# Esquema.net
KiCad netlist of a schematic drawn in EAGLE
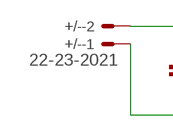
[diagram p0: schematic, sheet 1, part 1 of 2]
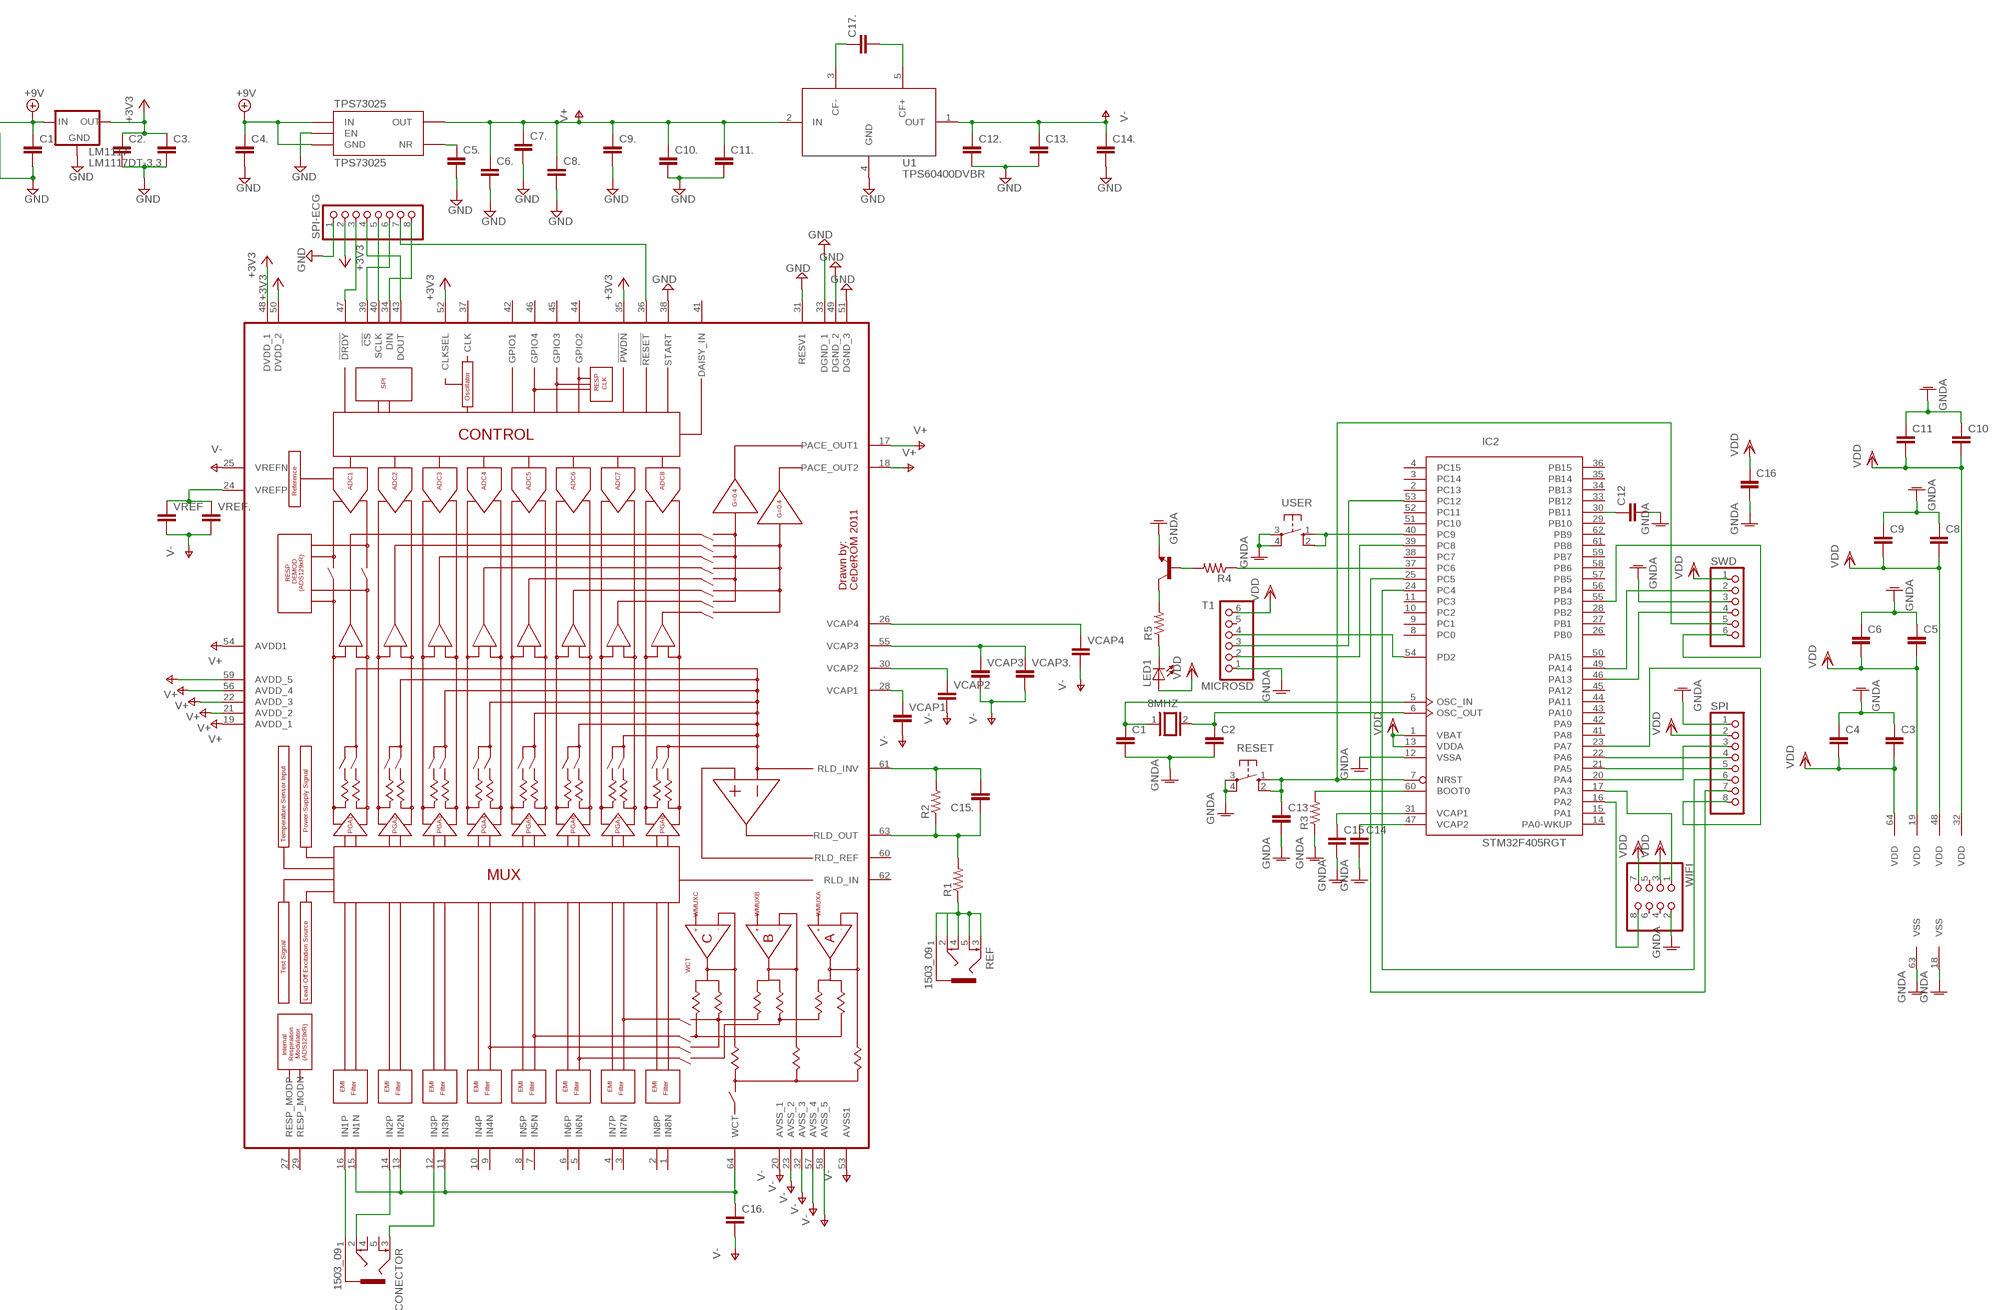
[diagram p1: schematic, sheet 1, part 2 of 2]

(export (version "E")
  (design (tool "Eeschema 10.0.6"))
  (components
    (comp (ref "+/-")
      (value "22-23-2021")
      (footprint "eagle-import:22-23-2021")
      (fields (field (name "MF") "MOLEX"))
      (libsource (lib "eagle-import") (part "22-23-2021"))
    )
    (comp (ref "8MHZ")
      (value "XTAL/S")
      (footprint "eagle-import:QS")
      (libsource (lib "eagle-import") (part "XTAL/S"))
    )
    (comp (ref "C1")
      (value "C-EUC0805K")
      (footprint "eagle-import:C0805K")
      (libsource (lib "eagle-import") (part "resistor_348_C-EUC0805K"))
    )
    (comp (ref "C1.")
      (value "C-EUC1206K")
      (footprint "eagle-import:C1206K")
      (libsource (lib "eagle-import") (part "C-EUC1206K"))
    )
    (comp (ref "C2")
      (value "C-EUC0805K")
      (footprint "eagle-import:C0805K")
      (libsource (lib "eagle-import") (part "resistor_348_C-EUC0805K"))
    )
    (comp (ref "C2.")
      (value "C-EUC1206K")
      (footprint "eagle-import:C1206K")
      (libsource (lib "eagle-import") (part "C-EUC1206K"))
    )
    (comp (ref "C3")
      (value "C-EUC1206K")
      (footprint "eagle-import:C1206K")
      (libsource (lib "eagle-import") (part "resistor_348_C-EUC1206K"))
    )
    (comp (ref "C3.")
      (value "C-EUC1206K")
      (footprint "eagle-import:C1206K")
      (libsource (lib "eagle-import") (part "C-EUC1206K"))
    )
    (comp (ref "C4")
      (value "C-EUC1206K")
      (footprint "eagle-import:C1206K")
      (libsource (lib "eagle-import") (part "resistor_348_C-EUC1206K"))
    )
    (comp (ref "C4.")
      (value "C-EUC1206K")
      (footprint "eagle-import:C1206K")
      (libsource (lib "eagle-import") (part "C-EUC1206K"))
    )
    (comp (ref "C5")
      (value "C-EUC1206K")
      (footprint "eagle-import:C1206K")
      (libsource (lib "eagle-import") (part "resistor_348_C-EUC1206K"))
    )
    (comp (ref "C5.")
      (value "C-EUC0805K")
      (footprint "eagle-import:C0805K")
      (libsource (lib "eagle-import") (part "C-EUC0805K"))
    )
    (comp (ref "C6")
      (value "C-EUC1206K")
      (footprint "eagle-import:C1206K")
      (libsource (lib "eagle-import") (part "resistor_348_C-EUC1206K"))
    )
    (comp (ref "C6.")
      (value "C-EUC1206K")
      (footprint "eagle-import:C1206K")
      (libsource (lib "eagle-import") (part "C-EUC1206K"))
    )
    (comp (ref "C7.")
      (value "C-EUC1206K")
      (footprint "eagle-import:C1206K")
      (libsource (lib "eagle-import") (part "C-EUC1206K"))
    )
    (comp (ref "C8")
      (value "C-EUC1206K")
      (footprint "eagle-import:C1206K")
      (libsource (lib "eagle-import") (part "resistor_348_C-EUC1206K"))
    )
    (comp (ref "C8.")
      (value "C-EUC1206K")
      (footprint "eagle-import:C1206K")
      (libsource (lib "eagle-import") (part "C-EUC1206K"))
    )
    (comp (ref "C9")
      (value "C-EUC1206K")
      (footprint "eagle-import:C1206K")
      (libsource (lib "eagle-import") (part "resistor_348_C-EUC1206K"))
    )
    (comp (ref "C9.")
      (value "C-EUC1206K")
      (footprint "eagle-import:C1206K")
      (libsource (lib "eagle-import") (part "C-EUC1206K"))
    )
    (comp (ref "C10")
      (value "C-EUC1206K")
      (footprint "eagle-import:C1206K")
      (libsource (lib "eagle-import") (part "resistor_348_C-EUC1206K"))
    )
    (comp (ref "C10.")
      (value "C-EUC1206K")
      (footprint "eagle-import:C1206K")
      (libsource (lib "eagle-import") (part "C-EUC1206K"))
    )
    (comp (ref "C11")
      (value "C-EUC1206K")
      (footprint "eagle-import:C1206K")
      (libsource (lib "eagle-import") (part "resistor_348_C-EUC1206K"))
    )
    (comp (ref "C11.")
      (value "C-EUC1206K")
      (footprint "eagle-import:C1206K")
      (libsource (lib "eagle-import") (part "C-EUC1206K"))
    )
    (comp (ref "C12")
      (value "C-EUC1206K")
      (footprint "eagle-import:C1206K")
      (libsource (lib "eagle-import") (part "resistor_348_C-EUC1206K"))
    )
    (comp (ref "C12.")
      (value "C-EUC1206K")
      (footprint "eagle-import:C1206K")
      (libsource (lib "eagle-import") (part "C-EUC1206K"))
    )
    (comp (ref "C13")
      (value "C-EUC1206K")
      (footprint "eagle-import:C1206K")
      (libsource (lib "eagle-import") (part "resistor_348_C-EUC1206K"))
    )
    (comp (ref "C13.")
      (value "C-EUC1206K")
      (footprint "eagle-import:C1206K")
      (libsource (lib "eagle-import") (part "C-EUC1206K"))
    )
    (comp (ref "C14")
      (value "C-EUC1206K")
      (footprint "eagle-import:C1206K")
      (libsource (lib "eagle-import") (part "resistor_348_C-EUC1206K"))
    )
    (comp (ref "C14.")
      (value "C-EUC1206K")
      (footprint "eagle-import:C1206K")
      (libsource (lib "eagle-import") (part "C-EUC1206K"))
    )
    (comp (ref "C15")
      (value "C-EUC1206K")
      (footprint "eagle-import:C1206K")
      (libsource (lib "eagle-import") (part "resistor_348_C-EUC1206K"))
    )
    (comp (ref "C15.")
      (value "C-EUC1206K")
      (footprint "eagle-import:C1206K")
      (libsource (lib "eagle-import") (part "resistor_348_C-EUC1206K"))
    )
    (comp (ref "C16")
      (value "C-EUC1206K")
      (footprint "eagle-import:C1206K")
      (libsource (lib "eagle-import") (part "resistor_348_C-EUC1206K"))
    )
    (comp (ref "C16.")
      (value "C-EUC0805K")
      (footprint "eagle-import:C0805K")
      (libsource (lib "eagle-import") (part "resistor_348_C-EUC0805K"))
    )
    (comp (ref "C17.")
      (value "C-EUC1206K")
      (footprint "eagle-import:C1206K")
      (libsource (lib "eagle-import") (part "C-EUC1206K"))
    )
    (comp (ref "CONECTOR")
      (value "1503_09")
      (footprint "eagle-import:1503_09")
      (libsource (lib "eagle-import") (part "1503_09"))
    )
    (comp (ref "IC2")
      (value "STM32F405RGT")
      (footprint "eagle-import:LQFP64")
      (libsource (lib "eagle-import") (part "STM32F405RTG"))
    )
    (comp (ref "LED1")
      (value "LEDCHIP-LED0805")
      (footprint "eagle-import:CHIP-LED0805")
      (libsource (lib "eagle-import") (part "LEDCHIP-LED0805"))
    )
    (comp (ref "LM1117")
      (value "LM1117DT-3.3")
      (footprint "eagle-import:TO252")
      (fields (field (name "MF") "Texas Instruments"))
      (libsource (lib "eagle-import") (part "LM1117?-DT3.3"))
    )
    (comp (ref "MICROSD")
      (value "PINHD-1X6")
      (footprint "eagle-import:1X06")
      (libsource (lib "eagle-import") (part "PINHD-1X6"))
    )
    (comp (ref "R1")
      (value "R-US_R1206")
      (footprint "eagle-import:R1206")
      (libsource (lib "eagle-import") (part "R-US_R1206"))
    )
    (comp (ref "R2")
      (value "R-US_R1206")
      (footprint "eagle-import:R1206")
      (libsource (lib "eagle-import") (part "R-US_R1206"))
    )
    (comp (ref "R3")
      (value "R-US_R1206")
      (footprint "eagle-import:R1206")
      (libsource (lib "eagle-import") (part "R-US_R1206"))
    )
    (comp (ref "R4")
      (value "R-US_R1206")
      (footprint "eagle-import:R1206")
      (libsource (lib "eagle-import") (part "R-US_R1206"))
    )
    (comp (ref "R5")
      (value "R-US_R1206")
      (footprint "eagle-import:R1206")
      (libsource (lib "eagle-import") (part "R-US_R1206"))
    )
    (comp (ref "REF")
      (value "1503_09")
      (footprint "eagle-import:1503_09")
      (libsource (lib "eagle-import") (part "1503_09"))
    )
    (comp (ref "RESET")
      (value "10-XX")
      (footprint "eagle-import:B3F-10XX")
      (fields (field (name "MPN") "B3F-1000"))
      (libsource (lib "eagle-import") (part "10-XX"))
    )
    (comp (ref "SPI")
      (value "PINHD-1X8")
      (footprint "eagle-import:1X08")
      (libsource (lib "eagle-import") (part "PINHD-1X8"))
    )
    (comp (ref "SPI-ECG")
      (value "PINHD-1X8")
      (footprint "eagle-import:1X08")
      (libsource (lib "eagle-import") (part "PINHD-1X8"))
    )
    (comp (ref "SWD")
      (value "PINHD-1X6")
      (footprint "eagle-import:1X06")
      (libsource (lib "eagle-import") (part "PINHD-1X6"))
    )
    (comp (ref "T1")
      (value "MMBT2222ALT1-NPN-SOT23-BEC")
      (footprint "eagle-import:SOT23-BEC")
      (libsource (lib "eagle-import") (part "-NPN-SOT23-BECMMBT2222ALT1"))
    )
    (comp (ref "TPS73025")
      (value "TPS73025")
      (footprint "eagle-import:SOT23-5L")
      (libsource (lib "eagle-import") (part "TPS73025"))
    )
    (comp (ref "U$1")
      (value "ADS1298*PAG*")
      (footprint "eagle-import:TQFP64")
      (libsource (lib "eagle-import") (part "ADS1298PAG"))
    )
    (comp (ref "U1")
      (value "TPS60400DVBR")
      (footprint "eagle-import:SOT23-5")
      (libsource (lib "eagle-import") (part "TPS60400DVBR"))
    )
    (comp (ref "USER")
      (value "10-XX")
      (footprint "eagle-import:B3F-10XX")
      (fields (field (name "MPN") "B3F-1000"))
      (libsource (lib "eagle-import") (part "10-XX"))
    )
    (comp (ref "VCAP1")
      (value "C-EUC0805K")
      (footprint "eagle-import:C0805K")
      (libsource (lib "eagle-import") (part "C-EUC0805K"))
    )
    (comp (ref "VCAP2")
      (value "C-EUC1206K")
      (footprint "eagle-import:C1206K")
      (libsource (lib "eagle-import") (part "C-EUC1206K"))
    )
    (comp (ref "VCAP3")
      (value "C-EUC1206K")
      (footprint "eagle-import:C1206K")
      (libsource (lib "eagle-import") (part "C-EUC1206K"))
    )
    (comp (ref "VCAP3.")
      (value "C-EUC1206K")
      (footprint "eagle-import:C1206K")
      (libsource (lib "eagle-import") (part "C-EUC1206K"))
    )
    (comp (ref "VCAP4")
      (value "C-EUC1206K")
      (footprint "eagle-import:C1206K")
      (libsource (lib "eagle-import") (part "C-EUC1206K"))
    )
    (comp (ref "VREF")
      (value "C-EUC1206K")
      (footprint "eagle-import:C1206K")
      (libsource (lib "eagle-import") (part "C-EUC1206K"))
    )
    (comp (ref "VREF.")
      (value "C-EUC1206K")
      (footprint "eagle-import:C1206K")
      (libsource (lib "eagle-import") (part "C-EUC1206K"))
    )
    (comp (ref "WIFI")
      (value "PINHD-2X4")
      (footprint "eagle-import:2X04")
      (libsource (lib "eagle-import") (part "PINHD-2X4"))
    )
  )
  (nets
    (net (code "1") (name "+3V3") (class "Default")
      (node (ref "C2.") (pin "1") (pinfunction "1_1") (pintype "passive"))
      (node (ref "C3.") (pin "1") (pinfunction "1_1") (pintype "passive"))
      (node (ref "LM1117") (pin "3") (pinfunction "OUT_3") (pintype "passive"))
      (node (ref "SPI-ECG") (pin "2") (pinfunction "2_2") (pintype "passive"))
      (node (ref "U$1") (pin "35") (pinfunction "~{PWDN}_35") (pintype "input"))
      (node (ref "U$1") (pin "48") (pinfunction "DVDD_1_48") (pintype "power_in"))
      (node (ref "U$1") (pin "50") (pinfunction "DVDD_2_50") (pintype "power_in"))
      (node (ref "U$1") (pin "52") (pinfunction "CLKSEL_52") (pintype "input"))
    )
    (net (code "2") (name "+9V") (class "Default")
      (node (ref "+/-") (pin "2") (pinfunction "S_2") (pintype "passive"))
      (node (ref "C1.") (pin "1") (pinfunction "1_1") (pintype "passive"))
      (node (ref "C4.") (pin "1") (pinfunction "1_1") (pintype "passive"))
      (node (ref "LM1117") (pin "2") (pinfunction "IN_2") (pintype "input"))
      (node (ref "TPS73025") (pin "1") (pinfunction "IN_1") (pintype "power_in"))
      (node (ref "TPS73025") (pin "2") (pinfunction "GND_2") (pintype "power_in"))
    )
    (net (code "3") (name "GND") (class "Default")
      (node (ref "+/-") (pin "1") (pinfunction "S_1") (pintype "passive"))
      (node (ref "C1.") (pin "2") (pinfunction "2_2") (pintype "passive"))
      (node (ref "C10.") (pin "2") (pinfunction "2_2") (pintype "passive"))
      (node (ref "C11.") (pin "2") (pinfunction "2_2") (pintype "passive"))
      (node (ref "C12.") (pin "2") (pinfunction "2_2") (pintype "passive"))
      (node (ref "C13.") (pin "2") (pinfunction "2_2") (pintype "passive"))
      (node (ref "C14.") (pin "2") (pinfunction "2_2") (pintype "passive"))
      (node (ref "C2.") (pin "2") (pinfunction "2_2") (pintype "passive"))
      (node (ref "C3.") (pin "2") (pinfunction "2_2") (pintype "passive"))
      (node (ref "C4.") (pin "2") (pinfunction "2_2") (pintype "passive"))
      (node (ref "C5.") (pin "2") (pinfunction "2_2") (pintype "passive"))
      (node (ref "C6.") (pin "2") (pinfunction "2_2") (pintype "passive"))
      (node (ref "C7.") (pin "2") (pinfunction "2_2") (pintype "passive"))
      (node (ref "C8.") (pin "2") (pinfunction "2_2") (pintype "passive"))
      (node (ref "C9.") (pin "2") (pinfunction "2_2") (pintype "passive"))
      (node (ref "LM1117") (pin "1") (pinfunction "GND_1") (pintype "input"))
      (node (ref "SPI-ECG") (pin "1") (pinfunction "1_1") (pintype "passive"))
      (node (ref "TPS73025") (pin "3") (pinfunction "EN_3") (pintype "bidirectional"))
      (node (ref "U$1") (pin "31") (pinfunction "RESV1_31") (pintype "input"))
      (node (ref "U$1") (pin "33") (pinfunction "DGND_1_33") (pintype "power_in"))
      (node (ref "U$1") (pin "38") (pinfunction "START_38") (pintype "input"))
      (node (ref "U$1") (pin "49") (pinfunction "DGND_2_49") (pintype "power_in"))
      (node (ref "U$1") (pin "51") (pinfunction "DGND_3_51") (pintype "power_in"))
      (node (ref "U1") (pin "4") (pinfunction "GND_4") (pintype "bidirectional"))
    )
    (net (code "4") (name "GNDA") (class "Default")
      (node (ref "C1") (pin "2") (pinfunction "2_2") (pintype "passive"))
      (node (ref "C10") (pin "1") (pinfunction "1_1") (pintype "passive"))
      (node (ref "C11") (pin "1") (pinfunction "1_1") (pintype "passive"))
      (node (ref "C12") (pin "2") (pinfunction "2_2") (pintype "passive"))
      (node (ref "C13") (pin "2") (pinfunction "2_2") (pintype "passive"))
      (node (ref "C14") (pin "2") (pinfunction "2_2") (pintype "passive"))
      (node (ref "C15") (pin "2") (pinfunction "2_2") (pintype "passive"))
      (node (ref "C16") (pin "2") (pinfunction "2_2") (pintype "passive"))
      (node (ref "C2") (pin "2") (pinfunction "2_2") (pintype "passive"))
      (node (ref "C3") (pin "1") (pinfunction "1_1") (pintype "passive"))
      (node (ref "C4") (pin "1") (pinfunction "1_1") (pintype "passive"))
      (node (ref "C5") (pin "1") (pinfunction "1_1") (pintype "passive"))
      (node (ref "C6") (pin "1") (pinfunction "1_1") (pintype "passive"))
      (node (ref "C8") (pin "1") (pinfunction "1_1") (pintype "passive"))
      (node (ref "C9") (pin "1") (pinfunction "1_1") (pintype "passive"))
      (node (ref "IC2") (pin "12") (pinfunction "VSSA_12") (pintype "power_in"))
      (node (ref "IC2") (pin "18") (pinfunction "VSS_18") (pintype "power_in"))
      (node (ref "IC2") (pin "63") (pinfunction "VSS_63") (pintype "power_in"))
      (node (ref "MICROSD") (pin "1") (pinfunction "1_1") (pintype "passive"))
      (node (ref "R3") (pin "1") (pinfunction "1_1") (pintype "passive"))
      (node (ref "RESET") (pin "3") (pinfunction "P_3") (pintype "passive"))
      (node (ref "RESET") (pin "4") (pinfunction "P1_4") (pintype "passive"))
      (node (ref "SPI") (pin "1") (pinfunction "1_1") (pintype "passive"))
      (node (ref "SWD") (pin "3") (pinfunction "3_3") (pintype "passive"))
      (node (ref "T1") (pin "E") (pinfunction "E_E") (pintype "passive"))
      (node (ref "USER") (pin "3") (pinfunction "P_3") (pintype "passive"))
      (node (ref "USER") (pin "4") (pinfunction "P1_4") (pintype "passive"))
      (node (ref "WIFI") (pin "2") (pinfunction "2_2") (pintype "passive"))
    )
    (net (code "5") (name "Net-(IC2A-BOOT0)") (class "Default")
      (node (ref "IC2") (pin "60") (pinfunction "BOOT0_60") (pintype "input"))
      (node (ref "R3") (pin "2") (pinfunction "2_2") (pintype "passive"))
    )
    (net (code "6") (name "Net-(IC2A-NRST)") (class "Default")
      (node (ref "C13") (pin "1") (pinfunction "1_1") (pintype "passive"))
      (node (ref "IC2") (pin "7") (pinfunction "NRST_7") (pintype "bidirectional"))
      (node (ref "RESET") (pin "1") (pinfunction "S_1") (pintype "passive"))
      (node (ref "RESET") (pin "2") (pinfunction "S1_2") (pintype "passive"))
      (node (ref "SWD") (pin "5") (pinfunction "5_5") (pintype "passive"))
    )
    (net (code "7") (name "Net-(IC2A-OSC_IN)") (class "Default")
      (node (ref "8MHZ") (pin "1") (pinfunction "1_1") (pintype "passive"))
      (node (ref "C1") (pin "1") (pinfunction "1_1") (pintype "passive"))
      (node (ref "IC2") (pin "5") (pinfunction "OSC_IN_5") (pintype "bidirectional"))
    )
    (net (code "8") (name "Net-(IC2A-OSC_OUT)") (class "Default")
      (node (ref "8MHZ") (pin "2") (pinfunction "2_2") (pintype "passive"))
      (node (ref "C2") (pin "1") (pinfunction "1_1") (pintype "passive"))
      (node (ref "IC2") (pin "6") (pinfunction "OSC_OUT_6") (pintype "bidirectional"))
    )
    (net (code "9") (name "Net-(IC2A-PA2)") (class "Default")
      (node (ref "IC2") (pin "16") (pinfunction "PA2_16") (pintype "bidirectional"))
      (node (ref "WIFI") (pin "8") (pinfunction "8_8") (pintype "passive"))
    )
    (net (code "10") (name "Net-(IC2A-PA3)") (class "Default")
      (node (ref "IC2") (pin "17") (pinfunction "PA3_17") (pintype "bidirectional"))
      (node (ref "WIFI") (pin "1") (pinfunction "1_1") (pintype "passive"))
    )
    (net (code "11") (name "Net-(IC2A-PA4)") (class "Default")
      (node (ref "IC2") (pin "20") (pinfunction "PA4_20") (pintype "bidirectional"))
      (node (ref "SPI") (pin "3") (pinfunction "3_3") (pintype "passive"))
    )
    (net (code "12") (name "Net-(IC2A-PA5)") (class "Default")
      (node (ref "IC2") (pin "21") (pinfunction "PA5_21") (pintype "bidirectional"))
      (node (ref "SPI") (pin "5") (pinfunction "5_5") (pintype "passive"))
    )
    (net (code "13") (name "Net-(IC2A-PA6)") (class "Default")
      (node (ref "IC2") (pin "22") (pinfunction "PA6_22") (pintype "bidirectional"))
      (node (ref "SPI") (pin "4") (pinfunction "4_4") (pintype "passive"))
    )
    (net (code "14") (name "Net-(IC2A-PA7)") (class "Default")
      (node (ref "IC2") (pin "23") (pinfunction "PA7_23") (pintype "bidirectional"))
      (node (ref "SPI") (pin "8") (pinfunction "8_8") (pintype "passive"))
    )
    (net (code "15") (name "Net-(IC2A-PA13)") (class "Default")
      (node (ref "IC2") (pin "46") (pinfunction "PA13_46") (pintype "bidirectional"))
      (node (ref "SWD") (pin "4") (pinfunction "4_4") (pintype "passive"))
    )
    (net (code "16") (name "Net-(IC2A-PA14)") (class "Default")
      (node (ref "IC2") (pin "49") (pinfunction "PA14_49") (pintype "bidirectional"))
      (node (ref "SWD") (pin "2") (pinfunction "2_2") (pintype "passive"))
    )
    (net (code "17") (name "Net-(IC2A-PB3)") (class "Default")
      (node (ref "IC2") (pin "55") (pinfunction "PB3_55") (pintype "bidirectional"))
      (node (ref "SWD") (pin "6") (pinfunction "6_6") (pintype "passive"))
    )
    (net (code "18") (name "Net-(IC2A-PB11)") (class "Default")
      (node (ref "C12") (pin "1") (pinfunction "1_1") (pintype "passive"))
      (node (ref "IC2") (pin "30") (pinfunction "PB11_30") (pintype "bidirectional"))
    )
    (net (code "19") (name "Net-(IC2A-PC4)") (class "Default")
      (node (ref "IC2") (pin "24") (pinfunction "PC4_24") (pintype "bidirectional"))
      (node (ref "SPI") (pin "6") (pinfunction "6_6") (pintype "passive"))
    )
    (net (code "20") (name "Net-(IC2A-PC5)") (class "Default")
      (node (ref "IC2") (pin "25") (pinfunction "PC5_25") (pintype "bidirectional"))
      (node (ref "SPI") (pin "7") (pinfunction "7_7") (pintype "passive"))
    )
    (net (code "21") (name "Net-(IC2A-PC6)") (class "Default")
      (node (ref "IC2") (pin "37") (pinfunction "PC6_37") (pintype "bidirectional"))
      (node (ref "R4") (pin "1") (pinfunction "1_1") (pintype "passive"))
    )
    (net (code "22") (name "Net-(IC2A-PC8)") (class "Default")
      (node (ref "IC2") (pin "39") (pinfunction "PC8_39") (pintype "bidirectional"))
      (node (ref "MICROSD") (pin "2") (pinfunction "2_2") (pintype "passive"))
    )
    (net (code "23") (name "Net-(IC2A-PC9)") (class "Default")
      (node (ref "IC2") (pin "40") (pinfunction "PC9_40") (pintype "bidirectional"))
      (node (ref "USER") (pin "1") (pinfunction "S_1") (pintype "passive"))
      (node (ref "USER") (pin "2") (pinfunction "S1_2") (pintype "passive"))
    )
    (net (code "24") (name "Net-(IC2A-PC12)") (class "Default")
      (node (ref "IC2") (pin "53") (pinfunction "PC12_53") (pintype "bidirectional"))
      (node (ref "MICROSD") (pin "3") (pinfunction "3_3") (pintype "passive"))
    )
    (net (code "25") (name "Net-(IC2A-PD2)") (class "Default")
      (node (ref "IC2") (pin "54") (pinfunction "PD2_54") (pintype "bidirectional"))
      (node (ref "MICROSD") (pin "4") (pinfunction "4_4") (pintype "passive"))
    )
    (net (code "26") (name "Net-(IC2A-VCAP1)") (class "Default")
      (node (ref "C15") (pin "1") (pinfunction "1_1") (pintype "passive"))
      (node (ref "IC2") (pin "31") (pinfunction "VCAP1_31") (pintype "power_in"))
    )
    (net (code "27") (name "Net-(IC2A-VCAP2)") (class "Default")
      (node (ref "C14") (pin "1") (pinfunction "1_1") (pintype "passive"))
      (node (ref "IC2") (pin "47") (pinfunction "VCAP2_47") (pintype "power_in"))
    )
    (net (code "28") (name "Net-(LED1-PadC)") (class "Default")
      (node (ref "LED1") (pin "C") (pinfunction "C_C") (pintype "passive"))
      (node (ref "R5") (pin "1") (pinfunction "1_1") (pintype "passive"))
    )
    (net (code "29") (name "Net-(R1-Pad1)") (class "Default")
      (node (ref "R1") (pin "1") (pinfunction "1_1") (pintype "passive"))
      (node (ref "REF") (pin "1") (pinfunction "1_1") (pintype "passive"))
      (node (ref "REF") (pin "2") (pinfunction "2_2") (pintype "passive"))
      (node (ref "REF") (pin "3") (pinfunction "3_3") (pintype "passive"))
      (node (ref "REF") (pin "4") (pinfunction "4_4") (pintype "passive"))
      (node (ref "REF") (pin "5") (pinfunction "5_5") (pintype "passive"))
    )
    (net (code "30") (name "Net-(R4-Pad2)") (class "Default")
      (node (ref "R4") (pin "2") (pinfunction "2_2") (pintype "passive"))
      (node (ref "T1") (pin "B") (pinfunction "B_B") (pintype "passive"))
    )
    (net (code "31") (name "Net-(R5-Pad2)") (class "Default")
      (node (ref "R5") (pin "2") (pinfunction "2_2") (pintype "passive"))
      (node (ref "T1") (pin "C") (pinfunction "C_C") (pintype "passive"))
    )
    (net (code "32") (name "Net-(TPS73025-NR)") (class "Default")
      (node (ref "C5.") (pin "1") (pinfunction "1_1") (pintype "passive"))
      (node (ref "TPS73025") (pin "4") (pinfunction "NR_4") (pintype "bidirectional"))
    )
    (net (code "33") (name "Net-(U$1-DIN)") (class "Default")
      (node (ref "SPI-ECG") (pin "8") (pinfunction "8_8") (pintype "passive"))
      (node (ref "U$1") (pin "34") (pinfunction "DIN_34") (pintype "input"))
    )
    (net (code "34") (name "Net-(U$1-DOUT)") (class "Default")
      (node (ref "SPI-ECG") (pin "4") (pinfunction "4_4") (pintype "passive"))
      (node (ref "U$1") (pin "43") (pinfunction "DOUT_43") (pintype "output"))
    )
    (net (code "35") (name "Net-(U$1-IN1N)") (class "Default")
      (node (ref "C16.") (pin "1") (pinfunction "1_1") (pintype "passive"))
      (node (ref "U$1") (pin "11") (pinfunction "IN3N_11") (pintype "input"))
      (node (ref "U$1") (pin "13") (pinfunction "IN2N_13") (pintype "input"))
      (node (ref "U$1") (pin "15") (pinfunction "IN1N_15") (pintype "input"))
      (node (ref "U$1") (pin "64") (pinfunction "WCT_64") (pintype "output"))
    )
    (net (code "36") (name "Net-(U$1-IN1P)") (class "Default")
      (node (ref "CONECTOR") (pin "1") (pinfunction "1_1") (pintype "passive"))
      (node (ref "U$1") (pin "16") (pinfunction "IN1P_16") (pintype "input"))
    )
    (net (code "37") (name "Net-(U$1-IN2P)") (class "Default")
      (node (ref "CONECTOR") (pin "2") (pinfunction "2_2") (pintype "passive"))
      (node (ref "U$1") (pin "14") (pinfunction "IN2P_14") (pintype "input"))
    )
    (net (code "38") (name "Net-(U$1-IN3P)") (class "Default")
      (node (ref "CONECTOR") (pin "3") (pinfunction "3_3") (pintype "passive"))
      (node (ref "U$1") (pin "12") (pinfunction "IN3P_12") (pintype "input"))
    )
    (net (code "39") (name "Net-(U$1-RLD_INV)") (class "Default")
      (node (ref "C15.") (pin "2") (pinfunction "2_2") (pintype "passive"))
      (node (ref "R2") (pin "2") (pinfunction "2_2") (pintype "passive"))
      (node (ref "U$1") (pin "61") (pinfunction "RLD_INV_61") (pintype "bidirectional"))
    )
    (net (code "40") (name "Net-(U$1-RLD_OUT)") (class "Default")
      (node (ref "C15.") (pin "1") (pinfunction "1_1") (pintype "passive"))
      (node (ref "R1") (pin "2") (pinfunction "2_2") (pintype "passive"))
      (node (ref "R2") (pin "1") (pinfunction "1_1") (pintype "passive"))
      (node (ref "U$1") (pin "63") (pinfunction "RLD_OUT_63") (pintype "output"))
    )
    (net (code "41") (name "Net-(U$1-SCLK)") (class "Default")
      (node (ref "SPI-ECG") (pin "5") (pinfunction "5_5") (pintype "passive"))
      (node (ref "U$1") (pin "40") (pinfunction "SCLK_40") (pintype "input"))
    )
    (net (code "42") (name "Net-(U$1-VCAP1)") (class "Default")
      (node (ref "U$1") (pin "28") (pinfunction "VCAP1_28") (pintype "bidirectional"))
      (node (ref "VCAP1") (pin "1") (pinfunction "1_1") (pintype "passive"))
    )
    (net (code "43") (name "Net-(U$1-VCAP2)") (class "Default")
      (node (ref "U$1") (pin "30") (pinfunction "VCAP2_30") (pintype "bidirectional"))
      (node (ref "VCAP2") (pin "1") (pinfunction "1_1") (pintype "passive"))
    )
    (net (code "44") (name "Net-(U$1-VCAP3)") (class "Default")
      (node (ref "U$1") (pin "55") (pinfunction "VCAP3_55") (pintype "bidirectional"))
      (node (ref "VCAP3") (pin "1") (pinfunction "1_1") (pintype "passive"))
      (node (ref "VCAP3.") (pin "1") (pinfunction "1_1") (pintype "passive"))
    )
    (net (code "45") (name "Net-(U$1-VCAP4)") (class "Default")
      (node (ref "U$1") (pin "26") (pinfunction "VCAP4_26") (pintype "bidirectional"))
      (node (ref "VCAP4") (pin "1") (pinfunction "1_1") (pintype "passive"))
    )
    (net (code "46") (name "Net-(U$1-VREFP)") (class "Default")
      (node (ref "U$1") (pin "24") (pinfunction "VREFP_24") (pintype "bidirectional"))
      (node (ref "VREF") (pin "1") (pinfunction "1_1") (pintype "passive"))
      (node (ref "VREF.") (pin "1") (pinfunction "1_1") (pintype "passive"))
    )
    (net (code "47") (name "Net-(U$1-~{CS})") (class "Default")
      (node (ref "SPI-ECG") (pin "6") (pinfunction "6_6") (pintype "passive"))
      (node (ref "U$1") (pin "39") (pinfunction "~{CS}_39") (pintype "input"))
    )
    (net (code "48") (name "Net-(U$1-~{DRDY})") (class "Default")
      (node (ref "SPI-ECG") (pin "3") (pinfunction "3_3") (pintype "passive"))
      (node (ref "U$1") (pin "47") (pinfunction "~{DRDY}_47") (pintype "output"))
    )
    (net (code "49") (name "Net-(U$1-~{RESET})") (class "Default")
      (node (ref "SPI-ECG") (pin "7") (pinfunction "7_7") (pintype "passive"))
      (node (ref "U$1") (pin "36") (pinfunction "~{RESET}_36") (pintype "input"))
    )
    (net (code "50") (name "Net-(U1-CF+)") (class "Default")
      (node (ref "C17.") (pin "2") (pinfunction "2_2") (pintype "passive"))
      (node (ref "U1") (pin "5") (pinfunction "CF+_5") (pintype "bidirectional"))
    )
    (net (code "51") (name "Net-(U1-CF-)") (class "Default")
      (node (ref "C17.") (pin "1") (pinfunction "1_1") (pintype "passive"))
      (node (ref "U1") (pin "3") (pinfunction "CF-_3") (pintype "bidirectional"))
    )
    (net (code "52") (name "V+") (class "Default")
      (node (ref "C10.") (pin "1") (pinfunction "1_1") (pintype "passive"))
      (node (ref "C11.") (pin "1") (pinfunction "1_1") (pintype "passive"))
      (node (ref "C6.") (pin "1") (pinfunction "1_1") (pintype "passive"))
      (node (ref "C7.") (pin "1") (pinfunction "1_1") (pintype "passive"))
      (node (ref "C8.") (pin "1") (pinfunction "1_1") (pintype "passive"))
      (node (ref "C9.") (pin "1") (pinfunction "1_1") (pintype "passive"))
      (node (ref "TPS73025") (pin "5") (pinfunction "OUT_5") (pintype "power_in"))
      (node (ref "U$1") (pin "17") (pinfunction "PACE_OUT1_17") (pintype "output"))
      (node (ref "U$1") (pin "18") (pinfunction "PACE_OUT2_18") (pintype "output"))
      (node (ref "U$1") (pin "19") (pinfunction "AVDD_1_19") (pintype "power_in"))
      (node (ref "U$1") (pin "21") (pinfunction "AVDD_2_21") (pintype "power_in"))
      (node (ref "U$1") (pin "22") (pinfunction "AVDD_3_22") (pintype "power_in"))
      (node (ref "U$1") (pin "54") (pinfunction "AVDD1_54") (pintype "power_in"))
      (node (ref "U$1") (pin "56") (pinfunction "AVDD_4_56") (pintype "power_in"))
      (node (ref "U$1") (pin "59") (pinfunction "AVDD_5_59") (pintype "power_in"))
      (node (ref "U1") (pin "2") (pinfunction "IN_2") (pintype "bidirectional"))
    )
    (net (code "53") (name "V-") (class "Default")
      (node (ref "C12.") (pin "1") (pinfunction "1_1") (pintype "passive"))
      (node (ref "C13.") (pin "1") (pinfunction "1_1") (pintype "passive"))
      (node (ref "C14.") (pin "1") (pinfunction "1_1") (pintype "passive"))
      (node (ref "C16.") (pin "2") (pinfunction "2_2") (pintype "passive"))
      (node (ref "U$1") (pin "20") (pinfunction "AVSS_1_20") (pintype "power_in"))
      (node (ref "U$1") (pin "23") (pinfunction "AVSS_2_23") (pintype "power_in"))
      (node (ref "U$1") (pin "25") (pinfunction "VREFN_25") (pintype "bidirectional"))
      (node (ref "U$1") (pin "32") (pinfunction "AVSS_3_32") (pintype "power_in"))
      (node (ref "U$1") (pin "53") (pinfunction "AVSS1_53") (pintype "power_in"))
      (node (ref "U$1") (pin "57") (pinfunction "AVSS_4_57") (pintype "power_in"))
      (node (ref "U$1") (pin "58") (pinfunction "AVSS_5_58") (pintype "power_in"))
      (node (ref "U1") (pin "1") (pinfunction "OUT_1") (pintype "bidirectional"))
      (node (ref "VCAP1") (pin "2") (pinfunction "2_2") (pintype "passive"))
      (node (ref "VCAP2") (pin "2") (pinfunction "2_2") (pintype "passive"))
      (node (ref "VCAP3") (pin "2") (pinfunction "2_2") (pintype "passive"))
      (node (ref "VCAP3.") (pin "2") (pinfunction "2_2") (pintype "passive"))
      (node (ref "VCAP4") (pin "2") (pinfunction "2_2") (pintype "passive"))
      (node (ref "VREF") (pin "2") (pinfunction "2_2") (pintype "passive"))
      (node (ref "VREF.") (pin "2") (pinfunction "2_2") (pintype "passive"))
    )
    (net (code "54") (name "VDD") (class "Default")
      (node (ref "C10") (pin "2") (pinfunction "2_2") (pintype "passive"))
      (node (ref "C11") (pin "2") (pinfunction "2_2") (pintype "passive"))
      (node (ref "C16") (pin "1") (pinfunction "1_1") (pintype "passive"))
      (node (ref "C3") (pin "2") (pinfunction "2_2") (pintype "passive"))
      (node (ref "C4") (pin "2") (pinfunction "2_2") (pintype "passive"))
      (node (ref "C5") (pin "2") (pinfunction "2_2") (pintype "passive"))
      (node (ref "C6") (pin "2") (pinfunction "2_2") (pintype "passive"))
      (node (ref "C8") (pin "2") (pinfunction "2_2") (pintype "passive"))
      (node (ref "C9") (pin "2") (pinfunction "2_2") (pintype "passive"))
      (node (ref "IC2") (pin "1") (pinfunction "VBAT_1") (pintype "power_in"))
      (node (ref "IC2") (pin "13") (pinfunction "VDDA_13") (pintype "power_in"))
      (node (ref "IC2") (pin "19") (pinfunction "VDD_19") (pintype "power_in"))
      (node (ref "IC2") (pin "32") (pinfunction "VDD_32") (pintype "power_in"))
      (node (ref "IC2") (pin "48") (pinfunction "VDD_48") (pintype "power_in"))
      (node (ref "IC2") (pin "64") (pinfunction "VDD_64") (pintype "power_in"))
      (node (ref "LED1") (pin "A") (pinfunction "A_A") (pintype "passive"))
      (node (ref "MICROSD") (pin "6") (pinfunction "6_6") (pintype "passive"))
      (node (ref "SPI") (pin "2") (pinfunction "2_2") (pintype "passive"))
      (node (ref "SWD") (pin "1") (pinfunction "1_1") (pintype "passive"))
      (node (ref "WIFI") (pin "3") (pinfunction "3_3") (pintype "passive"))
      (node (ref "WIFI") (pin "7") (pinfunction "7_7") (pintype "passive"))
    )
    (net (code "55") (name "unconnected-(CONECTOR-Pad4)") (class "Default")
      (node (ref "CONECTOR") (pin "4") (pinfunction "4_4") (pintype "passive"))
    )
    (net (code "56") (name "unconnected-(CONECTOR-Pad5)") (class "Default")
      (node (ref "CONECTOR") (pin "5") (pinfunction "5_5") (pintype "passive"))
    )
    (net (code "57") (name "unconnected-(IC2A-PA0-WKUP-Pad14)") (class "Default")
      (node (ref "IC2") (pin "14") (pinfunction "PA0-WKUP_14") (pintype "bidirectional"))
    )
    (net (code "58") (name "unconnected-(IC2A-PA1-Pad15)") (class "Default")
      (node (ref "IC2") (pin "15") (pinfunction "PA1_15") (pintype "bidirectional"))
    )
    (net (code "59") (name "unconnected-(IC2A-PA8-Pad41)") (class "Default")
      (node (ref "IC2") (pin "41") (pinfunction "PA8_41") (pintype "bidirectional"))
    )
    (net (code "60") (name "unconnected-(IC2A-PA9-Pad42)") (class "Default")
      (node (ref "IC2") (pin "42") (pinfunction "PA9_42") (pintype "bidirectional"))
    )
    (net (code "61") (name "unconnected-(IC2A-PA10-Pad43)") (class "Default")
      (node (ref "IC2") (pin "43") (pinfunction "PA10_43") (pintype "bidirectional"))
    )
    (net (code "62") (name "unconnected-(IC2A-PA11-Pad44)") (class "Default")
      (node (ref "IC2") (pin "44") (pinfunction "PA11_44") (pintype "bidirectional"))
    )
    (net (code "63") (name "unconnected-(IC2A-PA12-Pad45)") (class "Default")
      (node (ref "IC2") (pin "45") (pinfunction "PA12_45") (pintype "bidirectional"))
    )
    (net (code "64") (name "unconnected-(IC2A-PA15-Pad50)") (class "Default")
      (node (ref "IC2") (pin "50") (pinfunction "PA15_50") (pintype "bidirectional"))
    )
    (net (code "65") (name "unconnected-(IC2A-PB0-Pad26)") (class "Default")
      (node (ref "IC2") (pin "26") (pinfunction "PB0_26") (pintype "bidirectional"))
    )
    (net (code "66") (name "unconnected-(IC2A-PB1-Pad27)") (class "Default")
      (node (ref "IC2") (pin "27") (pinfunction "PB1_27") (pintype "bidirectional"))
    )
    (net (code "67") (name "unconnected-(IC2A-PB2-Pad28)") (class "Default")
      (node (ref "IC2") (pin "28") (pinfunction "PB2_28") (pintype "bidirectional"))
    )
    (net (code "68") (name "unconnected-(IC2A-PB4-Pad56)") (class "Default")
      (node (ref "IC2") (pin "56") (pinfunction "PB4_56") (pintype "bidirectional"))
    )
    (net (code "69") (name "unconnected-(IC2A-PB5-Pad57)") (class "Default")
      (node (ref "IC2") (pin "57") (pinfunction "PB5_57") (pintype "bidirectional"))
    )
    (net (code "70") (name "unconnected-(IC2A-PB6-Pad58)") (class "Default")
      (node (ref "IC2") (pin "58") (pinfunction "PB6_58") (pintype "bidirectional"))
    )
    (net (code "71") (name "unconnected-(IC2A-PB7-Pad59)") (class "Default")
      (node (ref "IC2") (pin "59") (pinfunction "PB7_59") (pintype "bidirectional"))
    )
    (net (code "72") (name "unconnected-(IC2A-PB8-Pad61)") (class "Default")
      (node (ref "IC2") (pin "61") (pinfunction "PB8_61") (pintype "bidirectional"))
    )
    (net (code "73") (name "unconnected-(IC2A-PB9-Pad62)") (class "Default")
      (node (ref "IC2") (pin "62") (pinfunction "PB9_62") (pintype "bidirectional"))
    )
    (net (code "74") (name "unconnected-(IC2A-PB10-Pad29)") (class "Default")
      (node (ref "IC2") (pin "29") (pinfunction "PB10_29") (pintype "bidirectional"))
    )
    (net (code "75") (name "unconnected-(IC2A-PB12-Pad33)") (class "Default")
      (node (ref "IC2") (pin "33") (pinfunction "PB12_33") (pintype "bidirectional"))
    )
    (net (code "76") (name "unconnected-(IC2A-PB13-Pad34)") (class "Default")
      (node (ref "IC2") (pin "34") (pinfunction "PB13_34") (pintype "bidirectional"))
    )
    (net (code "77") (name "unconnected-(IC2A-PB14-Pad35)") (class "Default")
      (node (ref "IC2") (pin "35") (pinfunction "PB14_35") (pintype "bidirectional"))
    )
    (net (code "78") (name "unconnected-(IC2A-PB15-Pad36)") (class "Default")
      (node (ref "IC2") (pin "36") (pinfunction "PB15_36") (pintype "bidirectional"))
    )
    (net (code "79") (name "unconnected-(IC2A-PC0-Pad8)") (class "Default")
      (node (ref "IC2") (pin "8") (pinfunction "PC0_8") (pintype "bidirectional"))
    )
    (net (code "80") (name "unconnected-(IC2A-PC1-Pad9)") (class "Default")
      (node (ref "IC2") (pin "9") (pinfunction "PC1_9") (pintype "bidirectional"))
    )
    (net (code "81") (name "unconnected-(IC2A-PC2-Pad10)") (class "Default")
      (node (ref "IC2") (pin "10") (pinfunction "PC2_10") (pintype "bidirectional"))
    )
    (net (code "82") (name "unconnected-(IC2A-PC3-Pad11)") (class "Default")
      (node (ref "IC2") (pin "11") (pinfunction "PC3_11") (pintype "bidirectional"))
    )
    (net (code "83") (name "unconnected-(IC2A-PC7-Pad38)") (class "Default")
      (node (ref "IC2") (pin "38") (pinfunction "PC7_38") (pintype "bidirectional"))
    )
    (net (code "84") (name "unconnected-(IC2A-PC10-Pad51)") (class "Default")
      (node (ref "IC2") (pin "51") (pinfunction "PC10_51") (pintype "bidirectional"))
    )
    (net (code "85") (name "unconnected-(IC2A-PC11-Pad52)") (class "Default")
      (node (ref "IC2") (pin "52") (pinfunction "PC11_52") (pintype "bidirectional"))
    )
    (net (code "86") (name "unconnected-(IC2A-PC13-Pad2)") (class "Default")
      (node (ref "IC2") (pin "2") (pinfunction "PC13_2") (pintype "bidirectional"))
    )
    (net (code "87") (name "unconnected-(IC2A-PC14-Pad3)") (class "Default")
      (node (ref "IC2") (pin "3") (pinfunction "PC14_3") (pintype "bidirectional"))
    )
    (net (code "88") (name "unconnected-(IC2A-PC15-Pad4)") (class "Default")
      (node (ref "IC2") (pin "4") (pinfunction "PC15_4") (pintype "bidirectional"))
    )
    (net (code "89") (name "unconnected-(MICROSD-Pad5)") (class "Default")
      (node (ref "MICROSD") (pin "5") (pinfunction "5_5") (pintype "passive"))
    )
    (net (code "90") (name "unconnected-(U$1-CLK-Pad37)") (class "Default")
      (node (ref "U$1") (pin "37") (pinfunction "CLK_37") (pintype "input"))
    )
    (net (code "91") (name "unconnected-(U$1-DAISY_IN-Pad41)") (class "Default")
      (node (ref "U$1") (pin "41") (pinfunction "DAISY_IN_41") (pintype "input"))
    )
    (net (code "92") (name "unconnected-(U$1-GPIO1-Pad42)") (class "Default")
      (node (ref "U$1") (pin "42") (pinfunction "GPIO1_42") (pintype "bidirectional"))
    )
    (net (code "93") (name "unconnected-(U$1-GPIO2-Pad44)") (class "Default")
      (node (ref "U$1") (pin "44") (pinfunction "GPIO2_44") (pintype "bidirectional"))
    )
    (net (code "94") (name "unconnected-(U$1-GPIO3-Pad45)") (class "Default")
      (node (ref "U$1") (pin "45") (pinfunction "GPIO3_45") (pintype "bidirectional"))
    )
    (net (code "95") (name "unconnected-(U$1-GPIO4-Pad46)") (class "Default")
      (node (ref "U$1") (pin "46") (pinfunction "GPIO4_46") (pintype "bidirectional"))
    )
    (net (code "96") (name "unconnected-(U$1-IN4N-Pad9)") (class "Default")
      (node (ref "U$1") (pin "9") (pinfunction "IN4N_9") (pintype "input"))
    )
    (net (code "97") (name "unconnected-(U$1-IN4P-Pad10)") (class "Default")
      (node (ref "U$1") (pin "10") (pinfunction "IN4P_10") (pintype "input"))
    )
    (net (code "98") (name "unconnected-(U$1-IN5N-Pad7)") (class "Default")
      (node (ref "U$1") (pin "7") (pinfunction "IN5N_7") (pintype "input"))
    )
    (net (code "99") (name "unconnected-(U$1-IN5P-Pad8)") (class "Default")
      (node (ref "U$1") (pin "8") (pinfunction "IN5P_8") (pintype "input"))
    )
    (net (code "100") (name "unconnected-(U$1-IN6N-Pad5)") (class "Default")
      (node (ref "U$1") (pin "5") (pinfunction "IN6N_5") (pintype "input"))
    )
    (net (code "101") (name "unconnected-(U$1-IN6P-Pad6)") (class "Default")
      (node (ref "U$1") (pin "6") (pinfunction "IN6P_6") (pintype "input"))
    )
    (net (code "102") (name "unconnected-(U$1-IN7N-Pad3)") (class "Default")
      (node (ref "U$1") (pin "3") (pinfunction "IN7N_3") (pintype "input"))
    )
    (net (code "103") (name "unconnected-(U$1-IN7P-Pad4)") (class "Default")
      (node (ref "U$1") (pin "4") (pinfunction "IN7P_4") (pintype "input"))
    )
    (net (code "104") (name "unconnected-(U$1-IN8N-Pad1)") (class "Default")
      (node (ref "U$1") (pin "1") (pinfunction "IN8N_1") (pintype "input"))
    )
    (net (code "105") (name "unconnected-(U$1-IN8P-Pad2)") (class "Default")
      (node (ref "U$1") (pin "2") (pinfunction "IN8P_2") (pintype "input"))
    )
    (net (code "106") (name "unconnected-(U$1-RESP_MODN-Pad29)") (class "Default")
      (node (ref "U$1") (pin "29") (pinfunction "RESP_MODN_29") (pintype "output"))
    )
    (net (code "107") (name "unconnected-(U$1-RESP_MODP-Pad27)") (class "Default")
      (node (ref "U$1") (pin "27") (pinfunction "RESP_MODP_27") (pintype "output"))
    )
    (net (code "108") (name "unconnected-(U$1-RLD_IN-Pad62)") (class "Default")
      (node (ref "U$1") (pin "62") (pinfunction "RLD_IN_62") (pintype "input"))
    )
    (net (code "109") (name "unconnected-(U$1-RLD_REF-Pad60)") (class "Default")
      (node (ref "U$1") (pin "60") (pinfunction "RLD_REF_60") (pintype "input"))
    )
    (net (code "110") (name "unconnected-(WIFI-Pad4)") (class "Default")
      (node (ref "WIFI") (pin "4") (pinfunction "4_4") (pintype "passive"))
    )
    (net (code "111") (name "unconnected-(WIFI-Pad5)") (class "Default")
      (node (ref "WIFI") (pin "5") (pinfunction "5_5") (pintype "passive"))
    )
    (net (code "112") (name "unconnected-(WIFI-Pad6)") (class "Default")
      (node (ref "WIFI") (pin "6") (pinfunction "6_6") (pintype "passive"))
    )
  )
)
